# 6502v2_lcd.net
KiCad netlist of a schematic drawn in EasyEDA
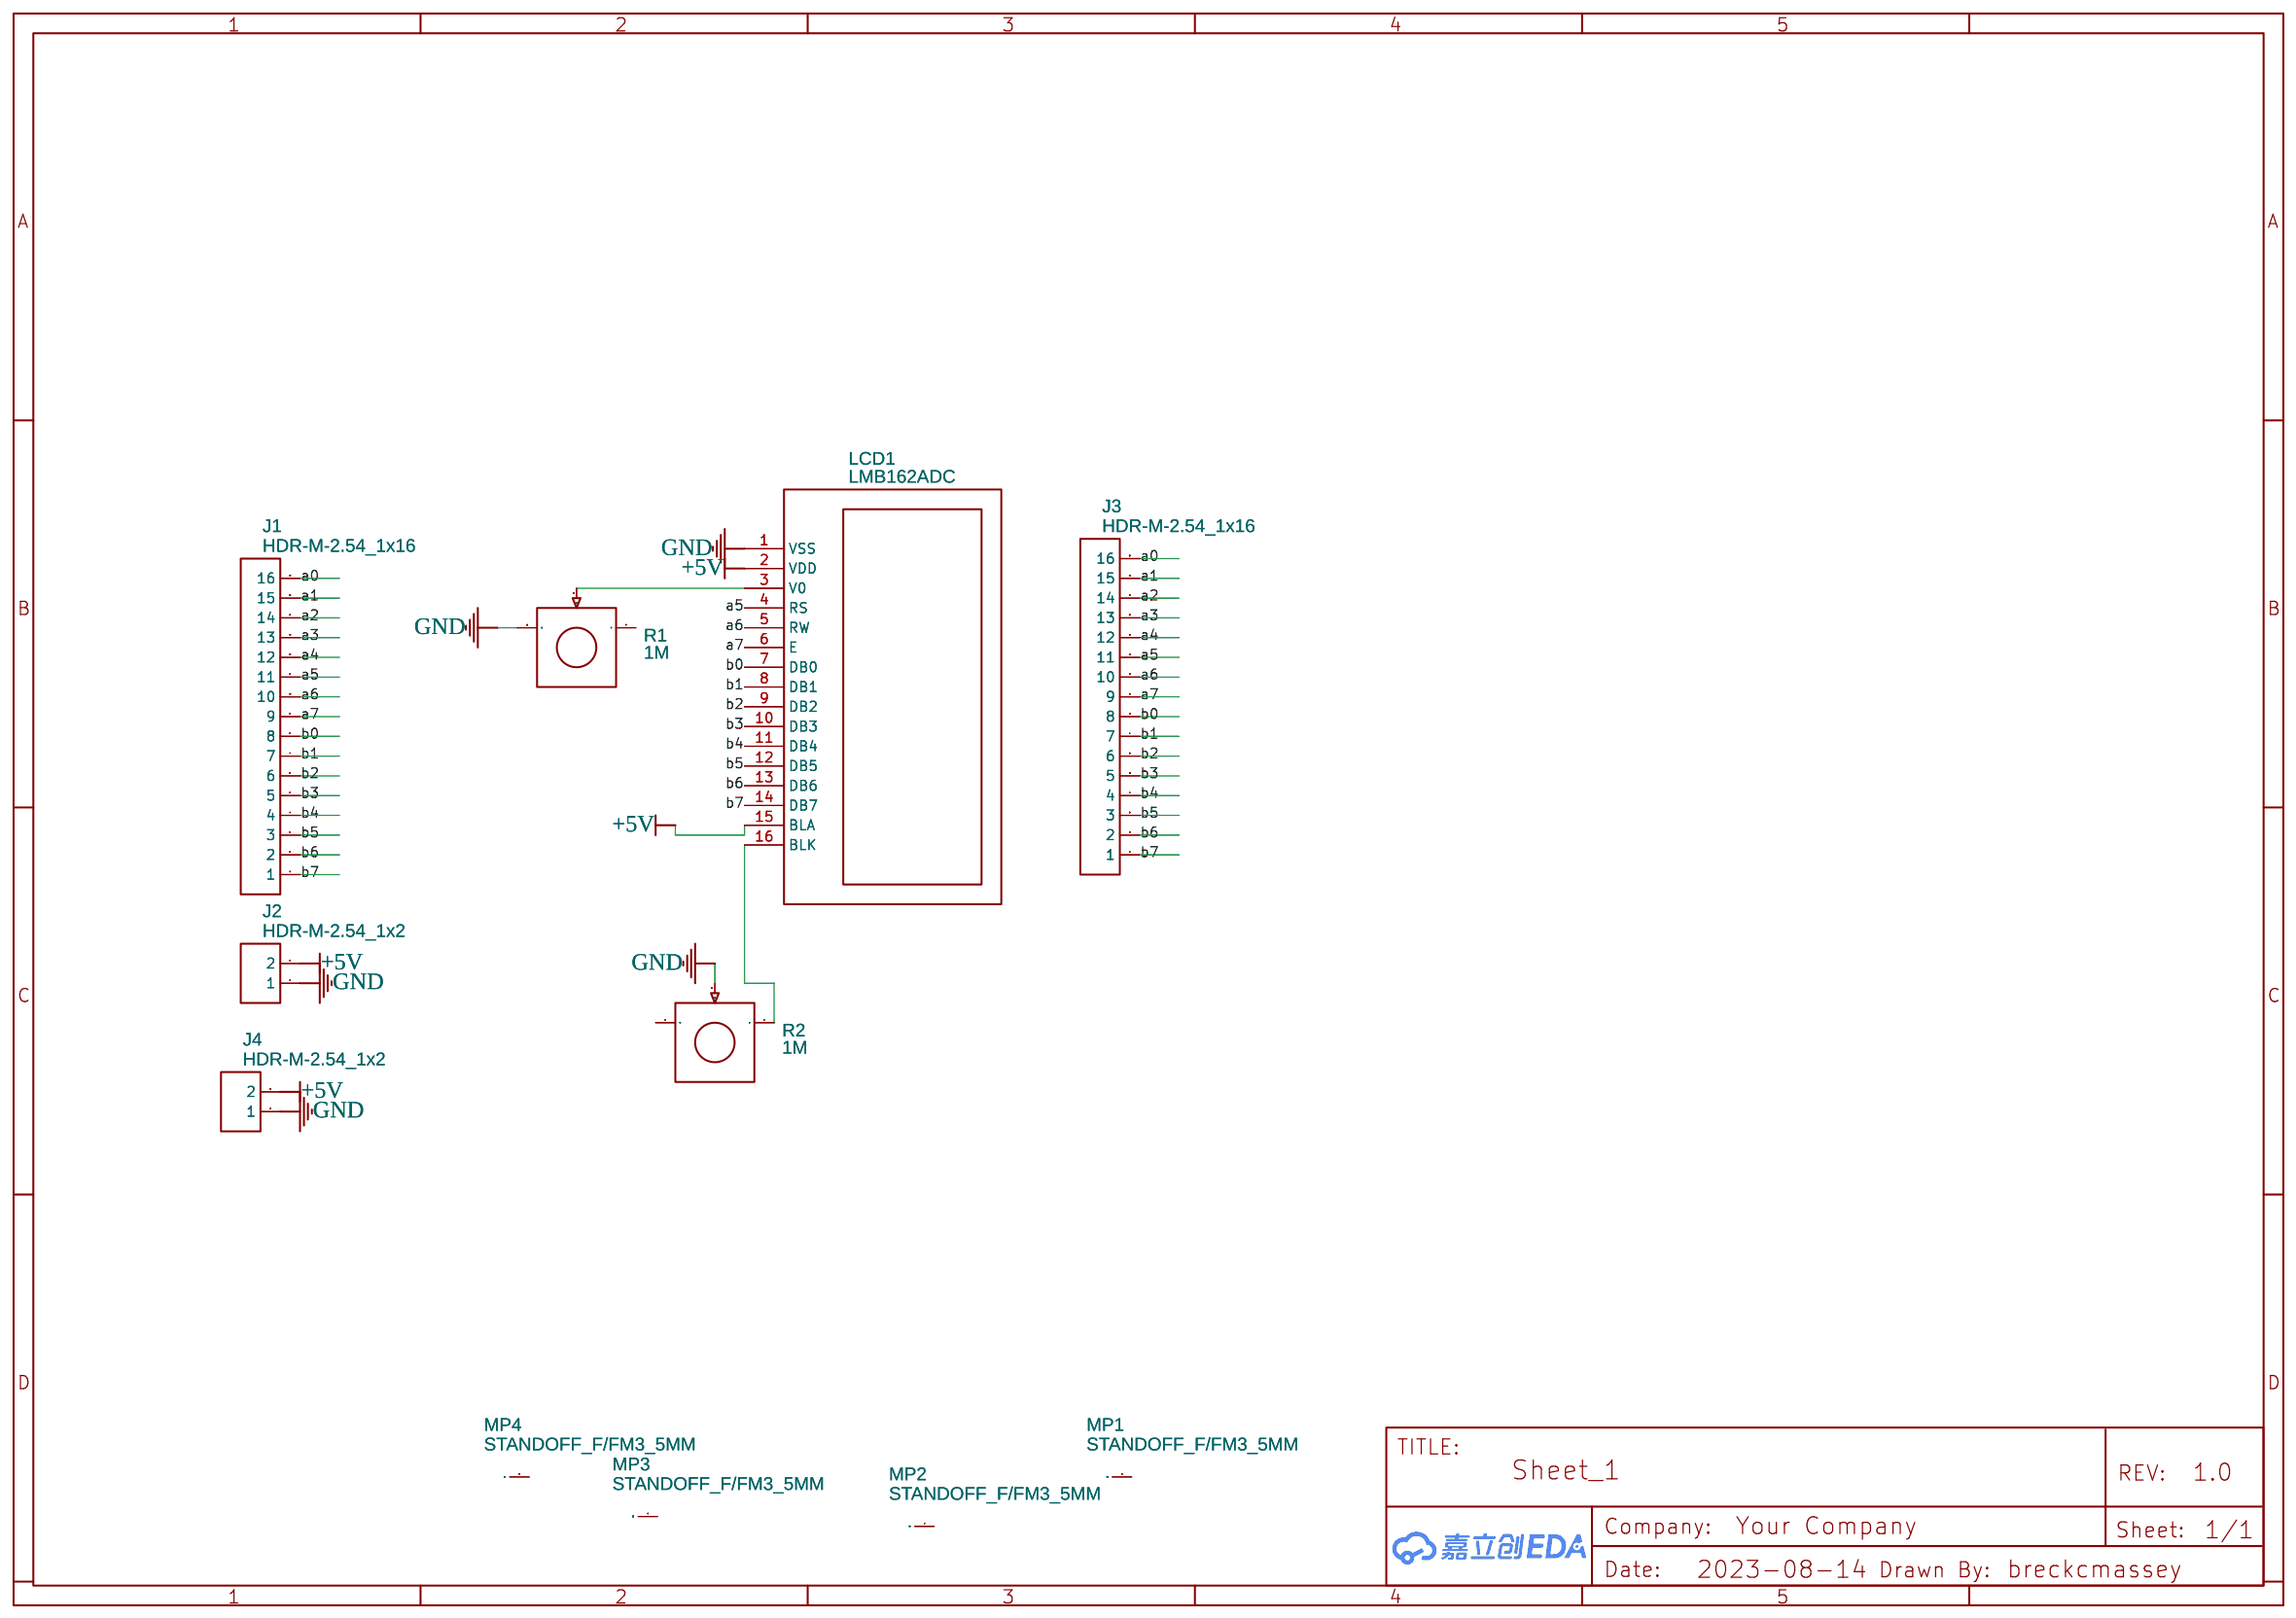
[diagram p0: schematic sheet]

(export (version "E")
  (design (tool "Eeschema 10.0.6"))
  (components
    (comp (ref "J1") (value "HDR-M-2.54_1x16") (libsource (lib "") (part "HDR-M-2.54_1x16")))
    (comp (ref "J2")
      (value "HDR-M-2.54_1x2")
      (fields (field (name "BOM_Supplier Part") "C124375"))
      (libsource (lib "") (part "HDR-M-2.54_1x2"))
    )
    (comp (ref "J3") (value "HDR-M-2.54_1x16") (libsource (lib "") (part "HDR-M-2.54_1x16")))
    (comp (ref "J4")
      (value "HDR-M-2.54_1x2")
      (fields (field (name "BOM_Supplier Part") "C124375"))
      (libsource (lib "") (part "HDR-M-2.54_1x2"))
    )
    (comp (ref "LCD1")
      (value "LMB162ADC")
      (fields (field (name "Manufacturer") "TOPWAY"))
      (libsource (lib "") (part "LMB162ADC"))
    )
    (comp (ref "MP1") (value "STANDOFF_F/FM3_5MM") (libsource (lib "") (part "STANDOFF_F/FM3_5MM")))
    (comp (ref "MP2") (value "STANDOFF_F/FM3_5MM") (libsource (lib "") (part "STANDOFF_F/FM3_5MM")))
    (comp (ref "MP3") (value "STANDOFF_F/FM3_5MM") (libsource (lib "") (part "STANDOFF_F/FM3_5MM")))
    (comp (ref "MP4") (value "STANDOFF_F/FM3_5MM") (libsource (lib "") (part "STANDOFF_F/FM3_5MM")))
    (comp (ref "R1")
      (value "1M")
      (fields
        (field (name "BOM_Manufacturer Part") "3386T-1-LS1MEG(105)")
        (field (name "BOM_Supplier Part") "2161422")
      )
      (libsource (lib "") (part "3/8 Inch Square Cermet Potentiometer 1MEG Ohms 1/2 Watt 1 Turn Thru Hole"))
    )
    (comp (ref "R2")
      (value "1M")
      (fields
        (field (name "BOM_Manufacturer Part") "3386T-1-LS1MEG(105)")
        (field (name "BOM_Supplier Part") "2161422")
      )
      (libsource (lib "") (part "3/8 Inch Square Cermet Potentiometer 1MEG Ohms 1/2 Watt 1 Turn Thru Hole"))
    )
  )
  (nets
    (net (code "1") (name "+5V") (class "Default")
      (node (ref "J2") (pin "2") (pinfunction "2_2") (pintype "unspecified"))
      (node (ref "J4") (pin "2") (pinfunction "2_2") (pintype "unspecified"))
      (node (ref "LCD1") (pin "15") (pinfunction "BLA_15") (pintype "unspecified"))
      (node (ref "LCD1") (pin "2") (pinfunction "VDD_2") (pintype "unspecified"))
    )
    (net (code "2") (name "/a0") (class "Default")
      (node (ref "J1") (pin "16") (pinfunction "16_16") (pintype "unspecified"))
      (node (ref "J3") (pin "16") (pinfunction "16_16") (pintype "unspecified"))
    )
    (net (code "3") (name "/a1") (class "Default")
      (node (ref "J1") (pin "15") (pinfunction "15_15") (pintype "unspecified"))
      (node (ref "J3") (pin "15") (pinfunction "15_15") (pintype "unspecified"))
    )
    (net (code "4") (name "/a2") (class "Default")
      (node (ref "J1") (pin "14") (pinfunction "14_14") (pintype "unspecified"))
      (node (ref "J3") (pin "14") (pinfunction "14_14") (pintype "unspecified"))
    )
    (net (code "5") (name "/a3") (class "Default")
      (node (ref "J1") (pin "13") (pinfunction "13_13") (pintype "unspecified"))
      (node (ref "J3") (pin "13") (pinfunction "13_13") (pintype "unspecified"))
    )
    (net (code "6") (name "/a4") (class "Default")
      (node (ref "J1") (pin "12") (pinfunction "12_12") (pintype "unspecified"))
      (node (ref "J3") (pin "12") (pinfunction "12_12") (pintype "unspecified"))
    )
    (net (code "7") (name "/a5") (class "Default")
      (node (ref "J1") (pin "11") (pinfunction "11_11") (pintype "unspecified"))
      (node (ref "J3") (pin "11") (pinfunction "11_11") (pintype "unspecified"))
      (node (ref "LCD1") (pin "4") (pinfunction "RS_4") (pintype "unspecified"))
    )
    (net (code "8") (name "/a6") (class "Default")
      (node (ref "J1") (pin "10") (pinfunction "10_10") (pintype "unspecified"))
      (node (ref "J3") (pin "10") (pinfunction "10_10") (pintype "unspecified"))
      (node (ref "LCD1") (pin "5") (pinfunction "RW_5") (pintype "unspecified"))
    )
    (net (code "9") (name "/a7") (class "Default")
      (node (ref "J1") (pin "9") (pinfunction "9_9") (pintype "unspecified"))
      (node (ref "J3") (pin "9") (pinfunction "9_9") (pintype "unspecified"))
      (node (ref "LCD1") (pin "6") (pinfunction "E_6") (pintype "unspecified"))
    )
    (net (code "10") (name "/b0") (class "Default")
      (node (ref "J1") (pin "8") (pinfunction "8_8") (pintype "unspecified"))
      (node (ref "J3") (pin "8") (pinfunction "8_8") (pintype "unspecified"))
      (node (ref "LCD1") (pin "7") (pinfunction "DB0_7") (pintype "unspecified"))
    )
    (net (code "11") (name "/b1") (class "Default")
      (node (ref "J1") (pin "7") (pinfunction "7_7") (pintype "unspecified"))
      (node (ref "J3") (pin "7") (pinfunction "7_7") (pintype "unspecified"))
      (node (ref "LCD1") (pin "8") (pinfunction "DB1_8") (pintype "unspecified"))
    )
    (net (code "12") (name "/b2") (class "Default")
      (node (ref "J1") (pin "6") (pinfunction "6_6") (pintype "unspecified"))
      (node (ref "J3") (pin "6") (pinfunction "6_6") (pintype "unspecified"))
      (node (ref "LCD1") (pin "9") (pinfunction "DB2_9") (pintype "unspecified"))
    )
    (net (code "13") (name "/b3") (class "Default")
      (node (ref "J1") (pin "5") (pinfunction "5_5") (pintype "unspecified"))
      (node (ref "J3") (pin "5") (pinfunction "5_5") (pintype "unspecified"))
      (node (ref "LCD1") (pin "10") (pinfunction "DB3_10") (pintype "unspecified"))
    )
    (net (code "14") (name "/b4") (class "Default")
      (node (ref "J1") (pin "4") (pinfunction "4_4") (pintype "unspecified"))
      (node (ref "J3") (pin "4") (pinfunction "4_4") (pintype "unspecified"))
      (node (ref "LCD1") (pin "11") (pinfunction "DB4_11") (pintype "unspecified"))
    )
    (net (code "15") (name "/b5") (class "Default")
      (node (ref "J1") (pin "3") (pinfunction "3_3") (pintype "unspecified"))
      (node (ref "J3") (pin "3") (pinfunction "3_3") (pintype "unspecified"))
      (node (ref "LCD1") (pin "12") (pinfunction "DB5_12") (pintype "unspecified"))
    )
    (net (code "16") (name "/b6") (class "Default")
      (node (ref "J1") (pin "2") (pinfunction "2_2") (pintype "unspecified"))
      (node (ref "J3") (pin "2") (pinfunction "2_2") (pintype "unspecified"))
      (node (ref "LCD1") (pin "13") (pinfunction "DB6_13") (pintype "unspecified"))
    )
    (net (code "17") (name "/b7") (class "Default")
      (node (ref "J1") (pin "1") (pinfunction "1_1") (pintype "unspecified"))
      (node (ref "J3") (pin "1") (pinfunction "1_1") (pintype "unspecified"))
      (node (ref "LCD1") (pin "14") (pinfunction "DB7_14") (pintype "unspecified"))
    )
    (net (code "18") (name "GND") (class "Default")
      (node (ref "J2") (pin "1") (pinfunction "1_1") (pintype "unspecified"))
      (node (ref "J4") (pin "1") (pinfunction "1_1") (pintype "unspecified"))
      (node (ref "LCD1") (pin "1") (pinfunction "VSS_1") (pintype "unspecified"))
      (node (ref "R1") (pin "3") (pinfunction "3_3") (pintype "unspecified"))
      (node (ref "R2") (pin "2") (pinfunction "2_2") (pintype "unspecified"))
    )
    (net (code "19") (name "Net-(LCD1-BLK)") (class "Default")
      (node (ref "LCD1") (pin "16") (pinfunction "BLK_16") (pintype "unspecified"))
      (node (ref "R2") (pin "1") (pinfunction "1_1") (pintype "unspecified"))
    )
    (net (code "20") (name "Net-(LCD1-V0)") (class "Default")
      (node (ref "LCD1") (pin "3") (pinfunction "V0_3") (pintype "unspecified"))
      (node (ref "R1") (pin "2") (pinfunction "2_2") (pintype "unspecified"))
    )
    (net (code "21") (name "unconnected-(MP1-P$1-Pad1)") (class "Default")
      (node (ref "MP1") (pin "1") (pinfunction "P$1_1") (pintype "bidirectional"))
    )
    (net (code "22") (name "unconnected-(MP2-P$1-Pad1)") (class "Default")
      (node (ref "MP2") (pin "1") (pinfunction "P$1_1") (pintype "bidirectional"))
    )
    (net (code "23") (name "unconnected-(MP3-P$1-Pad1)") (class "Default")
      (node (ref "MP3") (pin "1") (pinfunction "P$1_1") (pintype "bidirectional"))
    )
    (net (code "24") (name "unconnected-(MP4-P$1-Pad1)") (class "Default")
      (node (ref "MP4") (pin "1") (pinfunction "P$1_1") (pintype "bidirectional"))
    )
    (net (code "25") (name "unconnected-(R1-Pad1)") (class "Default")
      (node (ref "R1") (pin "1") (pinfunction "1_1") (pintype "unspecified"))
    )
    (net (code "26") (name "unconnected-(R2-Pad3)") (class "Default")
      (node (ref "R2") (pin "3") (pinfunction "3_3") (pintype "unspecified"))
    )
  )
)
